# LPCB225_-_POWER_DOWN_CONTROLLER.net
KiCad netlist of a schematic drawn in Altium Designer
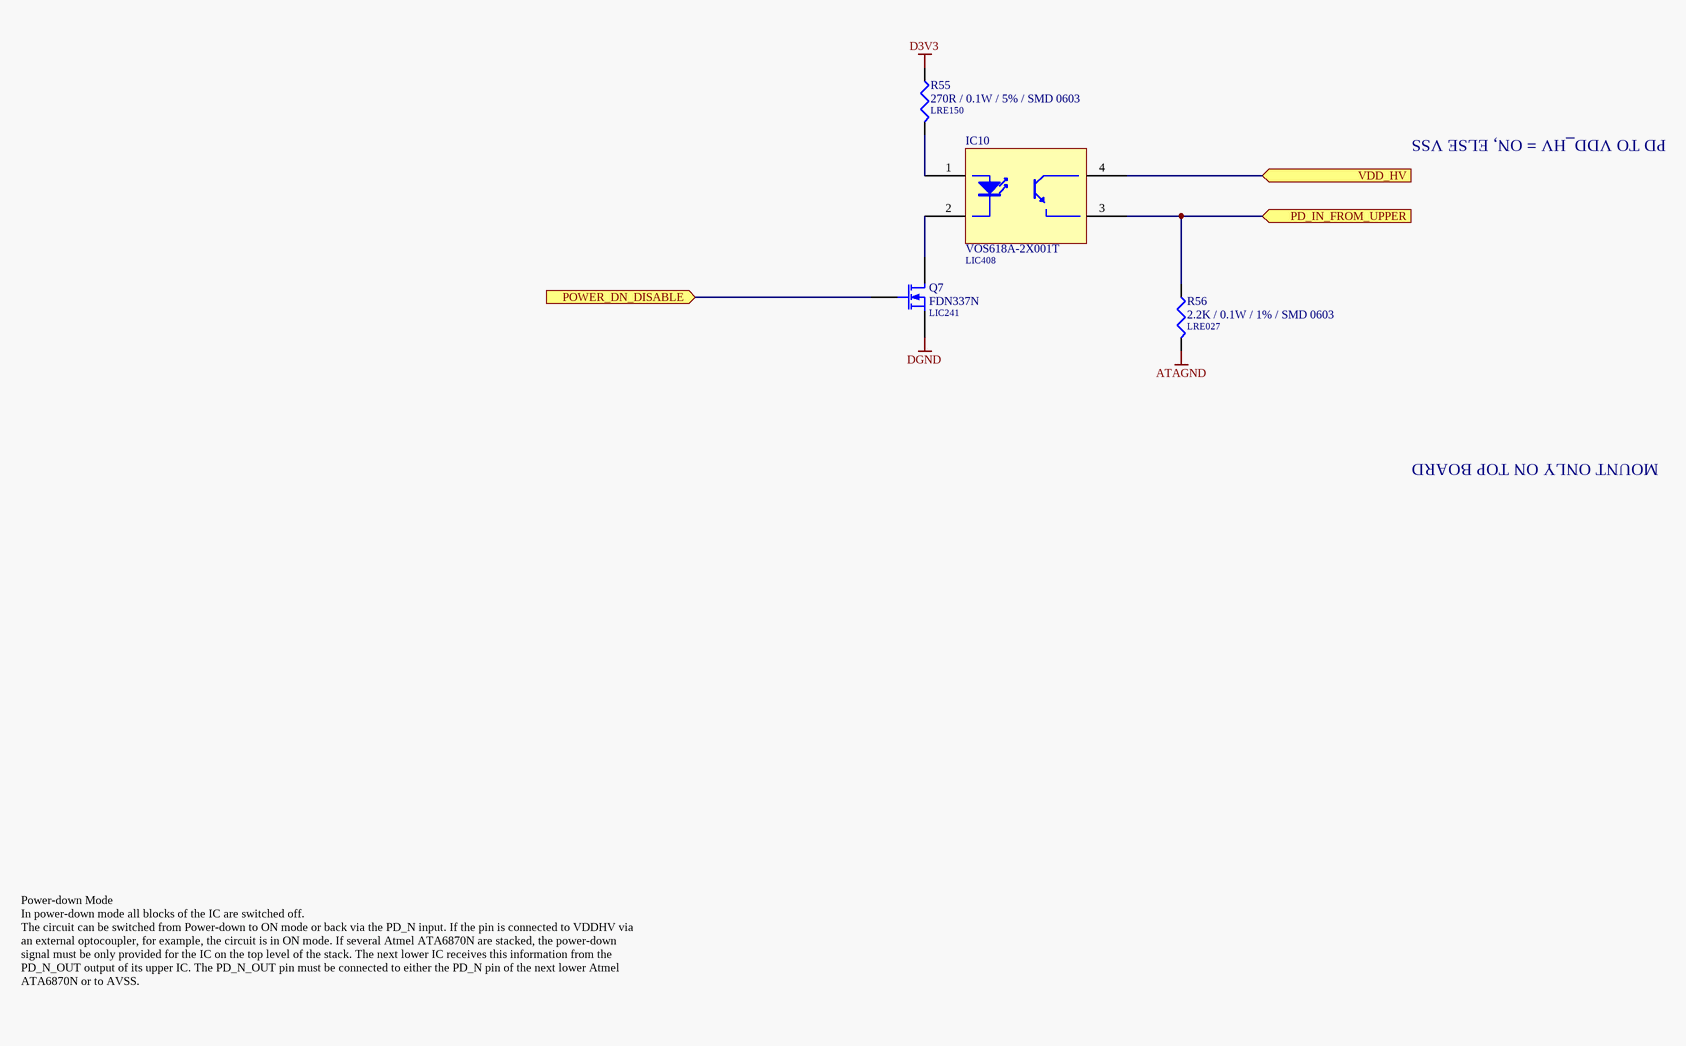
[diagram p0: LPCB225 - POWER DOWN CONTROLLER.SchDoc]

(export (version "E")
  (design (tool "Eeschema 10.0.6"))
  (components
    (comp (ref "IC10")
      (value "VOS618A-2X001T")
      (footprint "LFP085__VOS618A")
      (description "IC, Optocoupler, SMD [LIC408]")
      (fields (field (name "LDL_NUMBER") "LIC408"))
      (libsource (lib "LDL_Semiconductors") (part "VOS618A-2X001T"))
    )
    (comp (ref "Q7")
      (value "FDN337N")
      (footprint "LFP021__SOT23")
      (description "FET, N Channel, Logic Level, SMD SOT23 [LIC241]")
      (fields (field (name "LDL_NUMBER") "LIC241"))
      (libsource (lib "LDL_Semiconductors") (part "FDN337N"))
    )
    (comp (ref "R55")
      (value "270R / 0.1W / 5% / SMD 0603")
      (footprint "LFP020__CR1608-0603-IPC7351_B")
      (description "Resistor, Ceramic Chip, 270R, 0.1W, 1%, SMD 0603 [LRE150]")
      (fields (field (name "LDL_NUMBER") "LRE150"))
      (libsource (lib "LDL_Resistors") (part "270R / 0.1W / 5% / SMD 0603"))
    )
    (comp (ref "R56")
      (value "2.2K / 0.1W / 1% / SMD 0603")
      (footprint "LFP020__CR1608-0603-IPC7351_B")
      (description "Resistor, Ceramic Chip, 2.2K, 0.1W, 1%, SMD 0603 [LRE027]")
      (fields (field (name "LDL_NUMBER") "LRE027"))
      (libsource (lib "LDL_Resistors") (part "2.2K / 0.1W / 1% / SMD 0603"))
    )
  )
  (nets
    (net (code "1") (name "/PD_IN_FROM_UPPER") (class "Default")
      (node (ref "IC10") (pin "3") (pintype "passive"))
      (node (ref "R56") (pin "2") (pintype "passive"))
    )
    (net (code "2") (name "/POWER_DN_DISABLE") (class "Default")
      (node (ref "Q7") (pin "1") (pinfunction "G_1") (pintype "passive"))
    )
    (net (code "3") (name "/VDD_HV") (class "Default") (node (ref "IC10") (pin "4") (pintype "passive")))
    (net (code "4") (name "ATAGND") (class "Default") (node (ref "R56") (pin "1") (pintype "passive")))
    (net (code "5") (name "D3V3") (class "Default") (node (ref "R55") (pin "2") (pintype "passive")))
    (net (code "6") (name "DGND") (class "Default")
      (node (ref "Q7") (pin "2") (pinfunction "S_2") (pintype "passive"))
    )
    (net (code "7") (name "Net-(IC10-A)") (class "Default")
      (node (ref "IC10") (pin "1") (pinfunction "A_1") (pintype "passive"))
      (node (ref "R55") (pin "1") (pintype "passive"))
    )
    (net (code "8") (name "Net-(IC10-K)") (class "Default")
      (node (ref "IC10") (pin "2") (pinfunction "K_2") (pintype "passive"))
      (node (ref "Q7") (pin "3") (pinfunction "D_3") (pintype "passive"))
    )
  )
)
